# ESP32.net
KiCad netlist of a schematic drawn in Altium Designer
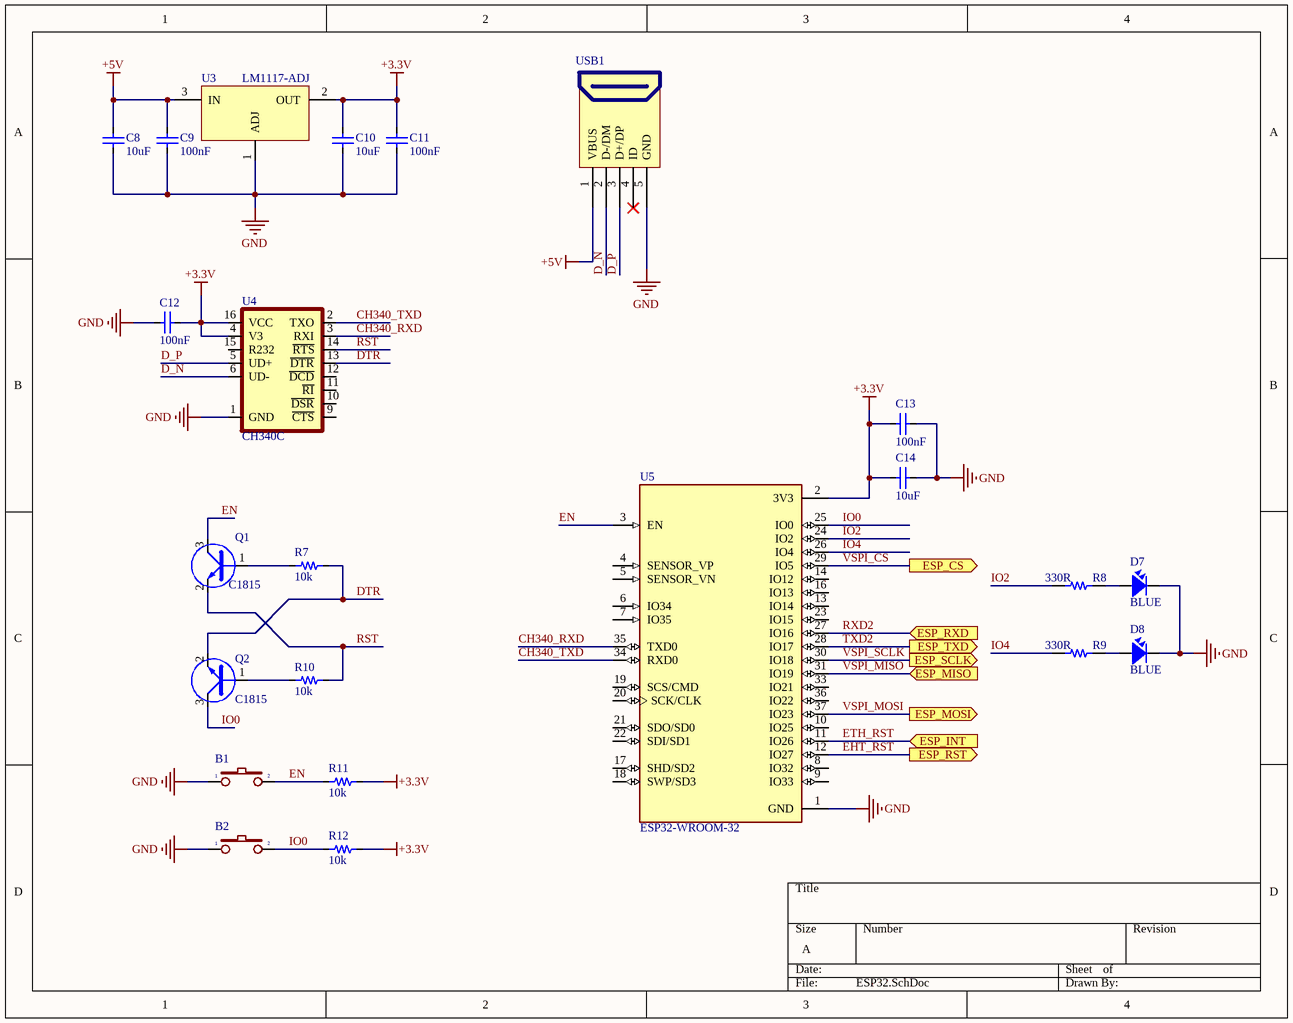
[diagram p0: ESP32.SchDoc]

(export (version "E")
  (design (tool "Eeschema 10.0.6"))
  (components
    (comp (ref "B1")
      (value "Button 3x4x2.5")
      (footprint "Button 3x4x2.5")
      (libsource (lib "Dung Library") (part "Button 3x4x2.5"))
    )
    (comp (ref "B2")
      (value "Button 3x4x2.5")
      (footprint "BUTTON NGHIENG")
      (libsource (lib "Dung Library") (part "Button 3x4x2.5"))
    )
    (comp (ref "C8")
      (value "10uF")
      (footprint "CAP_0603")
      (description "Capacitor")
      (fields (field (name "PUBLISHER") "Altium Limited"))
      (libsource (lib "My Library") (part "CapSMD"))
    )
    (comp (ref "C9")
      (value "100nF")
      (footprint "CAP_0603")
      (description "Capacitor")
      (fields (field (name "PUBLISHER") "Altium Limited"))
      (libsource (lib "My Library") (part "CapSMD"))
    )
    (comp (ref "C10")
      (value "10uF")
      (footprint "CAP_0603")
      (description "Capacitor")
      (fields (field (name "PUBLISHER") "Altium Limited"))
      (libsource (lib "My Library") (part "CapSMD"))
    )
    (comp (ref "C11")
      (value "100nF")
      (footprint "CAP_0603")
      (description "Capacitor")
      (fields (field (name "PUBLISHER") "Altium Limited"))
      (libsource (lib "My Library") (part "CapSMD"))
    )
    (comp (ref "C12")
      (value "100nF")
      (footprint "CAP_0603")
      (description "Capacitor")
      (fields (field (name "PUBLISHER") "Altium Limited"))
      (libsource (lib "My Library") (part "CapSMD"))
    )
    (comp (ref "C13")
      (value "100nF")
      (footprint "CAP_0603")
      (description "Capacitor")
      (fields (field (name "PUBLISHER") "Altium Limited"))
      (libsource (lib "My Library") (part "CapSMD"))
    )
    (comp (ref "C14")
      (value "10uF")
      (footprint "CAP_0603")
      (description "Capacitor")
      (fields (field (name "PUBLISHER") "Altium Limited"))
      (libsource (lib "My Library") (part "CapSMD"))
    )
    (comp (ref "D7")
      (value "BLUE")
      (footprint "LED-0603-Green")
      (description "LED Single colour Green and Red")
      (libsource (lib "My Library") (part "LED"))
    )
    (comp (ref "D8")
      (value "BLUE")
      (footprint "LED-0603-Green")
      (description "LED Single colour Green and Red")
      (libsource (lib "My Library") (part "LED"))
    )
    (comp (ref "Q1")
      (value "C1815")
      (footprint "SOT23D")
      (description "NPN 600mW, ECB")
      (libsource (lib "") (part "2SC1815_1"))
    )
    (comp (ref "Q2")
      (value "C1815")
      (footprint "SOT23D")
      (description "NPN 600mW, ECB")
      (libsource (lib "My Library") (part "2SC1815"))
    )
    (comp (ref "R7")
      (value "10k")
      (footprint "RES-SMD-0603")
      (description "Resistor")
      (fields
        (field (name "MANUFACTURER") "Generic Components")
        (field (name "PUBLISHER") "Altium Hobart Technology Centre")
      )
      (libsource (lib "My Library") (part "Resistor - SMD"))
    )
    (comp (ref "R8")
      (value "330R")
      (footprint "RES-SMD-0603")
      (description "Resistor")
      (fields
        (field (name "MANUFACTURER") "Generic Components")
        (field (name "PUBLISHER") "Altium Hobart Technology Centre")
      )
      (libsource (lib "") (part "Resistor - SMD_1"))
    )
    (comp (ref "R9")
      (value "330R")
      (footprint "RES-SMD-0603")
      (description "Resistor")
      (fields
        (field (name "MANUFACTURER") "Generic Components")
        (field (name "PUBLISHER") "Altium Hobart Technology Centre")
      )
      (libsource (lib "") (part "Resistor - SMD_1"))
    )
    (comp (ref "R10")
      (value "10k")
      (footprint "RES-SMD-0603")
      (description "Resistor")
      (fields
        (field (name "MANUFACTURER") "Generic Components")
        (field (name "PUBLISHER") "Altium Hobart Technology Centre")
      )
      (libsource (lib "My Library") (part "Resistor - SMD"))
    )
    (comp (ref "R11")
      (value "10k")
      (footprint "RES-SMD-0603")
      (description "Resistor")
      (fields
        (field (name "MANUFACTURER") "Generic Components")
        (field (name "PUBLISHER") "Altium Hobart Technology Centre")
      )
      (libsource (lib "My Library") (part "Resistor - SMD"))
    )
    (comp (ref "R12")
      (value "10k")
      (footprint "RES-SMD-0603")
      (description "Resistor")
      (fields
        (field (name "MANUFACTURER") "Generic Components")
        (field (name "PUBLISHER") "Altium Hobart Technology Centre")
      )
      (libsource (lib "My Library") (part "Resistor - SMD"))
    )
    (comp (ref "U3")
      (value "LM1117-ADJ")
      (footprint "LM1117-SOP")
      (description "800mA Low-Dropout Linear Regulator")
      (fields (field (name "CREATOR") "Nguyen Ba Bien"))
      (libsource (lib "My Library") (part "LM1117-ADJ"))
    )
    (comp (ref "U4")
      (value "CH340C")
      (footprint "SO16")
      (description "USB to serial chip CH340")
      (fields (field (name "MF") "WCH"))
      (libsource (lib "My Library") (part "CH340C"))
    )
    (comp (ref "U5")
      (value "ESP32-WROOM-32")
      (footprint "ESP32_UE")
      (description "Bluetooth, WiFi Transceiver Module 2.4GHz ~ 2.5GHz Surface Mount")
      (fields (field (name "MF") "Espressif Systems") (field (name "DIGI-KEY_PART_NUMBER") "1904-1010-1-ND"))
      (libsource (lib "My Library") (part "ESP32-WROOM-32"))
    )
    (comp (ref "USB1")
      (value "USB Micro 5p DIP")
      (footprint "USB Micro 5p DIP")
      (description "USB Type B")
      (libsource (lib "Altium_Lib_by_KhueNguyenCreator") (part "USB Micro 5p DIP"))
    )
  )
  (nets
    (net (code "1") (name "+3.3V") (class "Default")
      (node (ref "C10") (pin "1") (pinfunction "1_1") (pintype "passive"))
      (node (ref "C11") (pin "1") (pinfunction "1_1") (pintype "passive"))
      (node (ref "C12") (pin "1") (pinfunction "1_1") (pintype "passive"))
      (node (ref "C13") (pin "1") (pinfunction "1_1") (pintype "passive"))
      (node (ref "C14") (pin "1") (pinfunction "1_1") (pintype "passive"))
      (node (ref "R11") (pin "1") (pinfunction "1_1") (pintype "passive"))
      (node (ref "R12") (pin "1") (pinfunction "1_1") (pintype "passive"))
      (node (ref "U3") (pin "2") (pinfunction "OUT_2") (pintype "passive"))
      (node (ref "U4") (pin "16") (pinfunction "VCC_16") (pintype "bidirectional"))
      (node (ref "U4") (pin "4") (pinfunction "V3_4") (pintype "bidirectional"))
      (node (ref "U5") (pin "2") (pinfunction "3V3_2") (pintype "power_in"))
    )
    (net (code "2") (name "+5V") (class "Default")
      (node (ref "C8") (pin "1") (pinfunction "1_1") (pintype "passive"))
      (node (ref "C9") (pin "1") (pinfunction "1_1") (pintype "passive"))
      (node (ref "U3") (pin "3") (pinfunction "IN_3") (pintype "passive"))
      (node (ref "USB1") (pin "1") (pinfunction "VBUS_1") (pintype "passive"))
    )
    (net (code "3") (name "/CH340_RXD") (class "Default")
      (node (ref "U4") (pin "3") (pinfunction "RXI_3") (pintype "bidirectional"))
      (node (ref "U5") (pin "35") (pinfunction "TXD0_35") (pintype "bidirectional"))
    )
    (net (code "4") (name "/CH340_TXD") (class "Default")
      (node (ref "U4") (pin "2") (pinfunction "TXO_2") (pintype "bidirectional"))
      (node (ref "U5") (pin "34") (pinfunction "RXD0_34") (pintype "bidirectional"))
    )
    (net (code "5") (name "/DTR") (class "Default")
      (node (ref "Q2") (pin "2") (pinfunction "E_2") (pintype "passive"))
      (node (ref "R7") (pin "1") (pinfunction "1_1") (pintype "passive"))
      (node (ref "U4") (pin "13") (pinfunction "~{DTR}_13") (pintype "bidirectional"))
    )
    (net (code "6") (name "/D_N") (class "Default")
      (node (ref "U4") (pin "6") (pinfunction "UD-_6") (pintype "bidirectional"))
      (node (ref "USB1") (pin "2") (pinfunction "D-/DM_2") (pintype "passive"))
    )
    (net (code "7") (name "/D_P") (class "Default")
      (node (ref "U4") (pin "5") (pinfunction "UD+_5") (pintype "bidirectional"))
      (node (ref "USB1") (pin "3") (pinfunction "D+/DP_3") (pintype "passive"))
    )
    (net (code "8") (name "/EHT_RST") (class "Default")
      (node (ref "U5") (pin "12") (pinfunction "IO27_12") (pintype "bidirectional"))
    )
    (net (code "9") (name "/EN") (class "Default")
      (node (ref "B1") (pin "2") (pinfunction "2_2") (pintype "passive"))
      (node (ref "Q1") (pin "3") (pinfunction "C_3") (pintype "passive"))
      (node (ref "R11") (pin "2") (pinfunction "2_2") (pintype "passive"))
      (node (ref "U5") (pin "3") (pinfunction "EN_3") (pintype "input"))
    )
    (net (code "10") (name "/ETH_RST") (class "Default")
      (node (ref "U5") (pin "11") (pinfunction "IO26_11") (pintype "bidirectional"))
    )
    (net (code "11") (name "/IO0") (class "Default")
      (node (ref "B2") (pin "2") (pinfunction "2_2") (pintype "passive"))
      (node (ref "Q2") (pin "3") (pinfunction "C_3") (pintype "passive"))
      (node (ref "R12") (pin "2") (pinfunction "2_2") (pintype "passive"))
      (node (ref "U5") (pin "25") (pinfunction "IO0_25") (pintype "bidirectional"))
    )
    (net (code "12") (name "/IO2") (class "Default")
      (node (ref "R8") (pin "2") (pinfunction "2_2") (pintype "passive"))
      (node (ref "U5") (pin "24") (pinfunction "IO2_24") (pintype "bidirectional"))
    )
    (net (code "13") (name "/IO4") (class "Default")
      (node (ref "R9") (pin "2") (pinfunction "2_2") (pintype "passive"))
      (node (ref "U5") (pin "26") (pinfunction "IO4_26") (pintype "bidirectional"))
    )
    (net (code "14") (name "/RST") (class "Default")
      (node (ref "Q1") (pin "2") (pinfunction "E_2") (pintype "passive"))
      (node (ref "R10") (pin "1") (pinfunction "1_1") (pintype "passive"))
      (node (ref "U4") (pin "14") (pinfunction "~{RTS}_14") (pintype "bidirectional"))
    )
    (net (code "15") (name "/RXD2") (class "Default")
      (node (ref "U5") (pin "27") (pinfunction "IO16_27") (pintype "bidirectional"))
    )
    (net (code "16") (name "/TXD2") (class "Default")
      (node (ref "U5") (pin "28") (pinfunction "IO17_28") (pintype "bidirectional"))
    )
    (net (code "17") (name "/VSPI_CS") (class "Default")
      (node (ref "U5") (pin "29") (pinfunction "IO5_29") (pintype "bidirectional"))
    )
    (net (code "18") (name "/VSPI_MISO") (class "Default")
      (node (ref "U5") (pin "31") (pinfunction "IO19_31") (pintype "bidirectional"))
    )
    (net (code "19") (name "/VSPI_MOSI") (class "Default")
      (node (ref "U5") (pin "37") (pinfunction "IO23_37") (pintype "bidirectional"))
    )
    (net (code "20") (name "/VSPI_SCLK") (class "Default")
      (node (ref "U5") (pin "30") (pinfunction "IO18_30") (pintype "bidirectional"))
    )
    (net (code "21") (name "GND") (class "Default")
      (node (ref "B1") (pin "1") (pinfunction "1_1") (pintype "passive"))
      (node (ref "B2") (pin "1") (pinfunction "1_1") (pintype "passive"))
      (node (ref "C10") (pin "2") (pinfunction "2_2") (pintype "passive"))
      (node (ref "C11") (pin "2") (pinfunction "2_2") (pintype "passive"))
      (node (ref "C12") (pin "2") (pinfunction "2_2") (pintype "passive"))
      (node (ref "C13") (pin "2") (pinfunction "2_2") (pintype "passive"))
      (node (ref "C14") (pin "2") (pinfunction "2_2") (pintype "passive"))
      (node (ref "C8") (pin "2") (pinfunction "2_2") (pintype "passive"))
      (node (ref "C9") (pin "2") (pinfunction "2_2") (pintype "passive"))
      (node (ref "D7") (pin "2") (pinfunction "2_2") (pintype "passive"))
      (node (ref "D8") (pin "2") (pinfunction "2_2") (pintype "passive"))
      (node (ref "U3") (pin "1") (pinfunction "ADJ_1") (pintype "passive"))
      (node (ref "U4") (pin "1") (pinfunction "GND_1") (pintype "bidirectional"))
      (node (ref "U5") (pin "1") (pinfunction "GND_1") (pintype "power_in"))
      (node (ref "USB1") (pin "5") (pinfunction "GND_5") (pintype "passive"))
    )
    (net (code "22") (name "Net-(D7-Pad1)") (class "Default")
      (node (ref "D7") (pin "1") (pinfunction "1_1") (pintype "passive"))
      (node (ref "R8") (pin "1") (pinfunction "1_1") (pintype "passive"))
    )
    (net (code "23") (name "Net-(D8-Pad1)") (class "Default")
      (node (ref "D8") (pin "1") (pinfunction "1_1") (pintype "passive"))
      (node (ref "R9") (pin "1") (pinfunction "1_1") (pintype "passive"))
    )
    (net (code "24") (name "Net-(Q1-B)") (class "Default")
      (node (ref "Q1") (pin "1") (pinfunction "B_1") (pintype "passive"))
      (node (ref "R7") (pin "2") (pinfunction "2_2") (pintype "passive"))
    )
    (net (code "25") (name "Net-(Q2-B)") (class "Default")
      (node (ref "Q2") (pin "1") (pinfunction "B_1") (pintype "passive"))
      (node (ref "R10") (pin "2") (pinfunction "2_2") (pintype "passive"))
    )
    (net (code "26") (name "unconnected-(U4-R232-Pad15)") (class "Default")
      (node (ref "U4") (pin "15") (pinfunction "R232_15") (pintype "bidirectional"))
    )
    (net (code "27") (name "unconnected-(U4-~{CTS}-Pad9)") (class "Default")
      (node (ref "U4") (pin "9") (pinfunction "~{CTS}_9") (pintype "bidirectional"))
    )
    (net (code "28") (name "unconnected-(U4-~{DCD}-Pad12)") (class "Default")
      (node (ref "U4") (pin "12") (pinfunction "~{DCD}_12") (pintype "bidirectional"))
    )
    (net (code "29") (name "unconnected-(U4-~{DSR}-Pad10)") (class "Default")
      (node (ref "U4") (pin "10") (pinfunction "~{DSR}_10") (pintype "bidirectional"))
    )
    (net (code "30") (name "unconnected-(U4-~{RI}-Pad11)") (class "Default")
      (node (ref "U4") (pin "11") (pinfunction "~{RI}_11") (pintype "bidirectional"))
    )
    (net (code "31") (name "unconnected-(U5-IO12-Pad14)") (class "Default")
      (node (ref "U5") (pin "14") (pinfunction "IO12_14") (pintype "bidirectional"))
    )
    (net (code "32") (name "unconnected-(U5-IO13-Pad16)") (class "Default")
      (node (ref "U5") (pin "16") (pinfunction "IO13_16") (pintype "bidirectional"))
    )
    (net (code "33") (name "unconnected-(U5-IO14-Pad13)") (class "Default")
      (node (ref "U5") (pin "13") (pinfunction "IO14_13") (pintype "bidirectional"))
    )
    (net (code "34") (name "unconnected-(U5-IO15-Pad23)") (class "Default")
      (node (ref "U5") (pin "23") (pinfunction "IO15_23") (pintype "bidirectional"))
    )
    (net (code "35") (name "unconnected-(U5-IO21-Pad33)") (class "Default")
      (node (ref "U5") (pin "33") (pinfunction "IO21_33") (pintype "bidirectional"))
    )
    (net (code "36") (name "unconnected-(U5-IO22-Pad36)") (class "Default")
      (node (ref "U5") (pin "36") (pinfunction "IO22_36") (pintype "bidirectional"))
    )
    (net (code "37") (name "unconnected-(U5-IO25-Pad10)") (class "Default")
      (node (ref "U5") (pin "10") (pinfunction "IO25_10") (pintype "bidirectional"))
    )
    (net (code "38") (name "unconnected-(U5-IO32-Pad8)") (class "Default")
      (node (ref "U5") (pin "8") (pinfunction "IO32_8") (pintype "bidirectional"))
    )
    (net (code "39") (name "unconnected-(U5-IO33-Pad9)") (class "Default")
      (node (ref "U5") (pin "9") (pinfunction "IO33_9") (pintype "bidirectional"))
    )
    (net (code "40") (name "unconnected-(U5-IO34-Pad6)") (class "Default")
      (node (ref "U5") (pin "6") (pinfunction "IO34_6") (pintype "input"))
    )
    (net (code "41") (name "unconnected-(U5-IO35-Pad7)") (class "Default")
      (node (ref "U5") (pin "7") (pinfunction "IO35_7") (pintype "input"))
    )
    (net (code "42") (name "unconnected-(U5-SCK{slash}CLK-Pad20)") (class "Default")
      (node (ref "U5") (pin "20") (pinfunction "SCK/CLK_20") (pintype "bidirectional"))
    )
    (net (code "43") (name "unconnected-(U5-SCS{slash}CMD-Pad19)") (class "Default")
      (node (ref "U5") (pin "19") (pinfunction "SCS/CMD_19") (pintype "bidirectional"))
    )
    (net (code "44") (name "unconnected-(U5-SDI{slash}SD1-Pad22)") (class "Default")
      (node (ref "U5") (pin "22") (pinfunction "SDI/SD1_22") (pintype "bidirectional"))
    )
    (net (code "45") (name "unconnected-(U5-SDO{slash}SD0-Pad21)") (class "Default")
      (node (ref "U5") (pin "21") (pinfunction "SDO/SD0_21") (pintype "bidirectional"))
    )
    (net (code "46") (name "unconnected-(U5-SENSOR_VN-Pad5)") (class "Default")
      (node (ref "U5") (pin "5") (pinfunction "SENSOR_VN_5") (pintype "input"))
    )
    (net (code "47") (name "unconnected-(U5-SENSOR_VP-Pad4)") (class "Default")
      (node (ref "U5") (pin "4") (pinfunction "SENSOR_VP_4") (pintype "input"))
    )
    (net (code "48") (name "unconnected-(U5-SHD{slash}SD2-Pad17)") (class "Default")
      (node (ref "U5") (pin "17") (pinfunction "SHD/SD2_17") (pintype "bidirectional"))
    )
    (net (code "49") (name "unconnected-(U5-SWP{slash}SD3-Pad18)") (class "Default")
      (node (ref "U5") (pin "18") (pinfunction "SWP/SD3_18") (pintype "bidirectional"))
    )
    (net (code "50") (name "unconnected-(USB1-ID-Pad4)") (class "Default")
      (node (ref "USB1") (pin "4") (pinfunction "ID_4") (pintype "passive+no_connect"))
    )
  )
)
